# Koroliov_v2.net
KiCad netlist of a schematic drawn in EAGLE
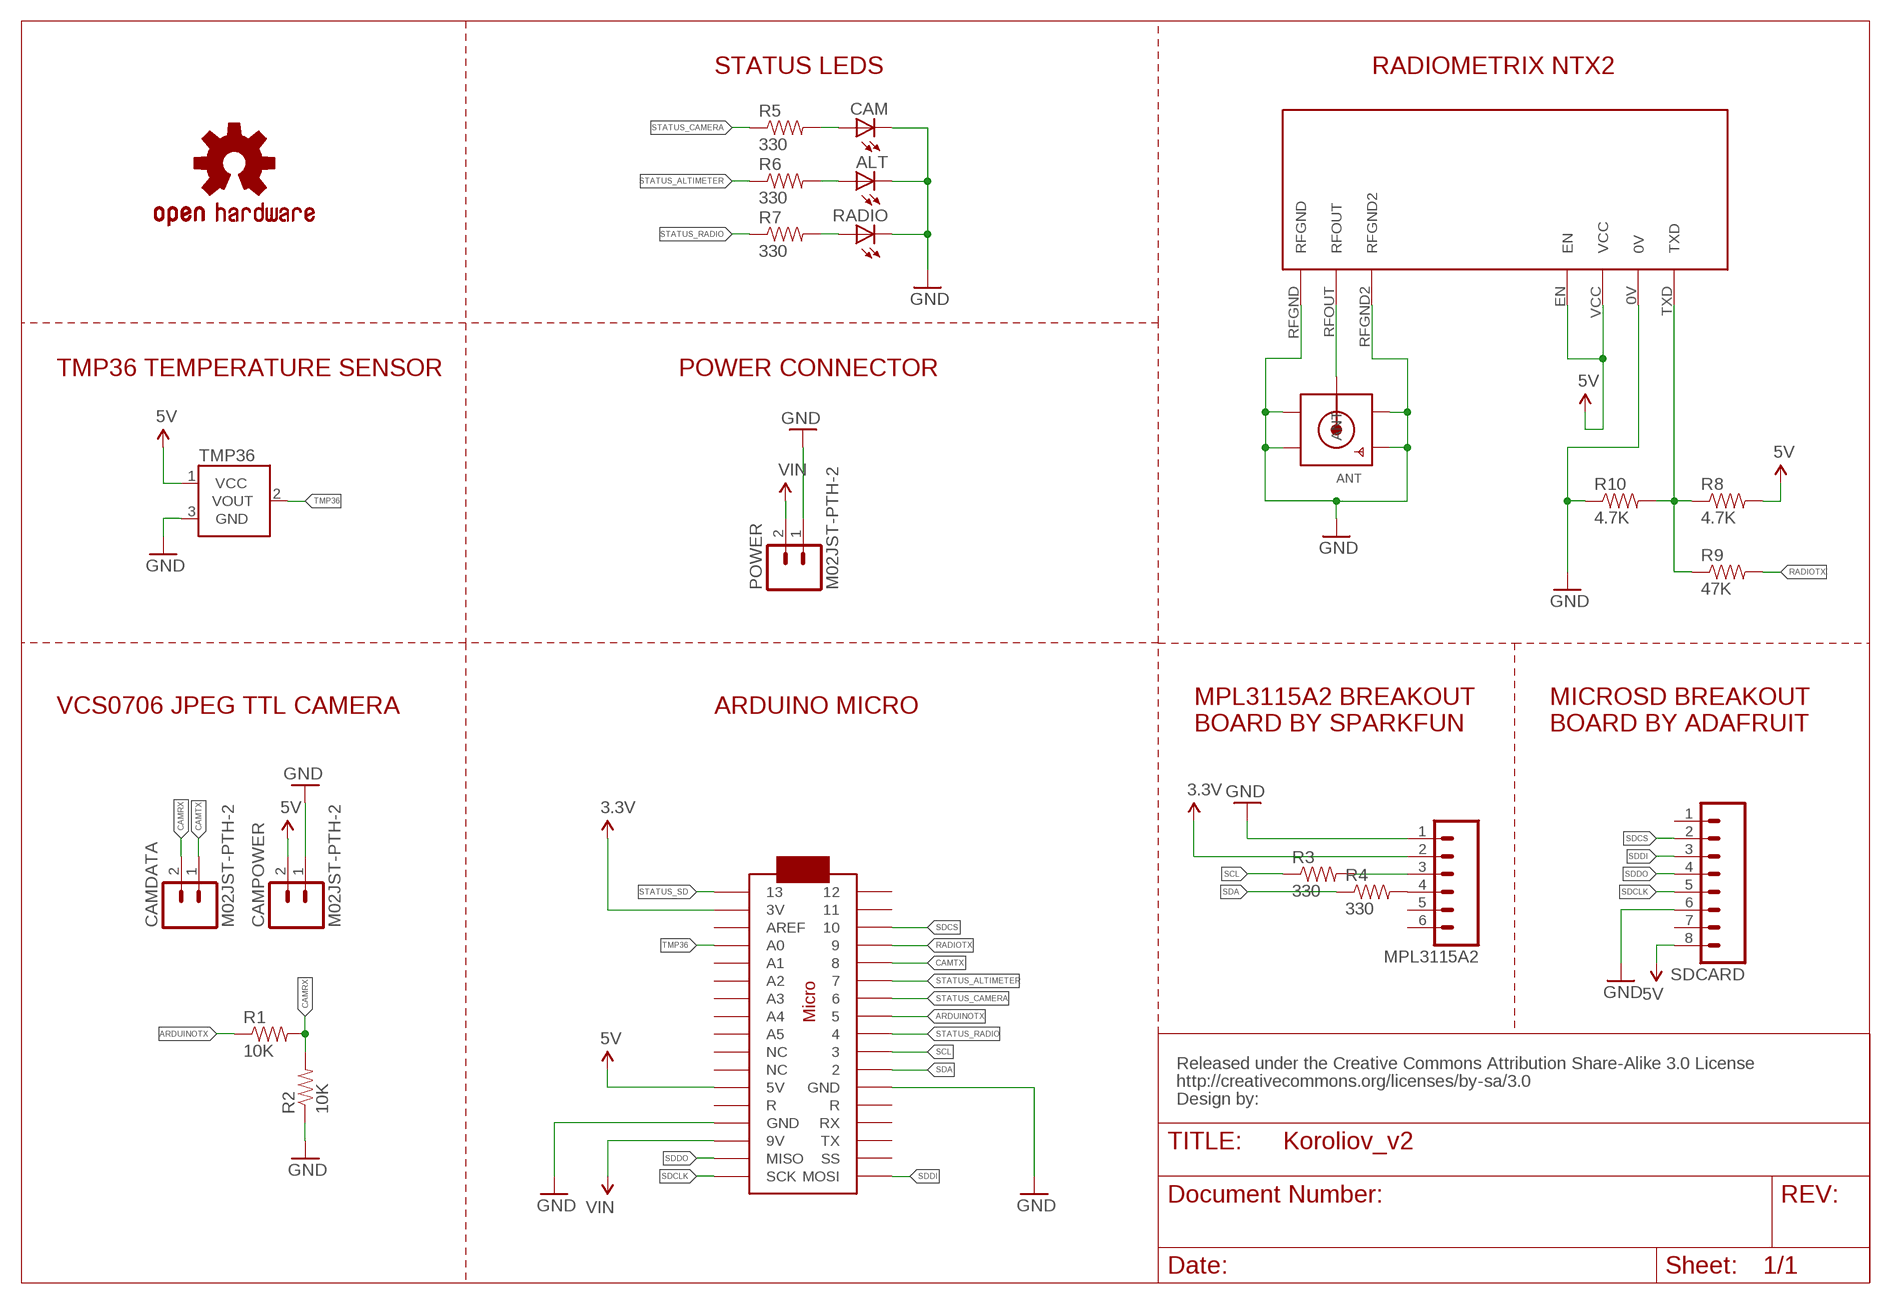
[diagram p0: schematic, sheet 1]

(export (version "E")
  (design (tool "Eeschema 10.0.6"))
  (components
    (comp (ref "ALT")
      (value "LED1206")
      (footprint "eagle-import:LED-1206")
      (libsource (lib "eagle-import") (part "LED1206"))
    )
    (comp (ref "ANT")
      (value "SMACONNECTOR_EDGE")
      (footprint "eagle-import:SMA_EDGELAUNCH")
      (libsource (lib "eagle-import") (part "SMACONNECTOR_EDGE"))
    )
    (comp (ref "ARDUINOMICRO")
      (value "ARDUINOMICRO")
      (footprint "eagle-import:ARDUINOMICRO")
      (libsource (lib "eagle-import") (part "ARDUINOMICRO"))
    )
    (comp (ref "CAM")
      (value "LED1206")
      (footprint "eagle-import:LED-1206")
      (libsource (lib "eagle-import") (part "LED1206"))
    )
    (comp (ref "CAMDATA")
      (value "M02JST-PTH-2")
      (footprint "eagle-import:JST-2-PTH")
      (libsource (lib "eagle-import") (part "M02JST-PTH-2"))
    )
    (comp (ref "CAMPOWER")
      (value "M02JST-PTH-2")
      (footprint "eagle-import:JST-2-PTH")
      (libsource (lib "eagle-import") (part "M02JST-PTH-2"))
    )
    (comp (ref "CC_TEXT1")
      (value "CREATIVE_COMMONS")
      (footprint "eagle-import:CREATIVE_COMMONS")
      (libsource (lib "eagle-import") (part "CREATIVE_COMMONS"))
    )
    (comp (ref "LOGO1")
      (value "OSHW-LOGOL")
      (footprint "eagle-import:OSHW-LOGO-L")
      (libsource (lib "eagle-import") (part "OSHW-LOGOL"))
    )
    (comp (ref "MPL3115A2")
      (value "M06SIP")
      (footprint "eagle-import:1X06")
      (libsource (lib "eagle-import") (part "M06SIP"))
    )
    (comp (ref "NTX2")
      (value "NTX2")
      (footprint "eagle-import:NTX2")
      (libsource (lib "eagle-import") (part "NTX2"))
    )
    (comp (ref "POWER")
      (value "M02JST-PTH-2")
      (footprint "eagle-import:JST-2-PTH")
      (libsource (lib "eagle-import") (part "M02JST-PTH-2"))
    )
    (comp (ref "R1")
      (value "10K")
      (footprint "eagle-import:1206")
      (libsource (lib "eagle-import") (part "RESISTOR1206"))
    )
    (comp (ref "R2")
      (value "10K")
      (footprint "eagle-import:1206")
      (libsource (lib "eagle-import") (part "RESISTOR1206"))
    )
    (comp (ref "R3")
      (value "330")
      (footprint "eagle-import:1206")
      (libsource (lib "eagle-import") (part "RESISTOR1206"))
    )
    (comp (ref "R4")
      (value "330")
      (footprint "eagle-import:1206")
      (libsource (lib "eagle-import") (part "RESISTOR1206"))
    )
    (comp (ref "R5")
      (value "330")
      (footprint "eagle-import:1206")
      (libsource (lib "eagle-import") (part "RESISTOR1206"))
    )
    (comp (ref "R6")
      (value "330")
      (footprint "eagle-import:1206")
      (libsource (lib "eagle-import") (part "RESISTOR1206"))
    )
    (comp (ref "R7")
      (value "330")
      (footprint "eagle-import:1206")
      (libsource (lib "eagle-import") (part "RESISTOR1206"))
    )
    (comp (ref "R8")
      (value "4.7K")
      (footprint "eagle-import:1206")
      (libsource (lib "eagle-import") (part "RESISTOR1206"))
    )
    (comp (ref "R9")
      (value "47K")
      (footprint "eagle-import:1206")
      (libsource (lib "eagle-import") (part "RESISTOR1206"))
    )
    (comp (ref "R10")
      (value "4.7K")
      (footprint "eagle-import:1206")
      (libsource (lib "eagle-import") (part "RESISTOR1206"))
    )
    (comp (ref "RADIO")
      (value "LED1206")
      (footprint "eagle-import:LED-1206")
      (libsource (lib "eagle-import") (part "LED1206"))
    )
    (comp (ref "SDCARD")
      (value "M081X08")
      (footprint "eagle-import:1X08")
      (libsource (lib "eagle-import") (part "M081X08"))
    )
    (comp (ref "TMP36")
      (value "TMP36GT9")
      (footprint "eagle-import:TO-92")
      (libsource (lib "eagle-import") (part "TMP36GT9"))
    )
  )
  (nets
    (net (code "1") (name "3.3V") (class "Default")
      (node (ref "ARDUINOMICRO") (pin "P$33") (pinfunction "3V_P$33") (pintype "bidirectional"))
      (node (ref "MPL3115A2") (pin "2") (pinfunction "2_2") (pintype "passive"))
    )
    (net (code "2") (name "5V") (class "Default")
      (node (ref "ARDUINOMICRO") (pin "P$23") (pinfunction "5V_P$23") (pintype "bidirectional"))
      (node (ref "CAMPOWER") (pin "2") (pinfunction "2_2") (pintype "passive"))
      (node (ref "NTX2") (pin "EN") (pinfunction "EN_EN") (pintype "bidirectional"))
      (node (ref "NTX2") (pin "VCC") (pinfunction "VCC_VCC") (pintype "bidirectional"))
      (node (ref "R8") (pin "2") (pinfunction "2_2") (pintype "passive"))
      (node (ref "SDCARD") (pin "8") (pinfunction "8_8") (pintype "passive"))
      (node (ref "TMP36") (pin "1") (pinfunction "VCC_1") (pintype "bidirectional"))
    )
    (net (code "3") (name "ARDUINOTX") (class "Default")
      (node (ref "ARDUINOMICRO") (pin "P$8") (pinfunction "5_P$8") (pintype "bidirectional"))
      (node (ref "R1") (pin "1") (pinfunction "1_1") (pintype "passive"))
    )
    (net (code "4") (name "CAMRX") (class "Default")
      (node (ref "CAMDATA") (pin "2") (pinfunction "2_2") (pintype "passive"))
      (node (ref "R1") (pin "2") (pinfunction "2_2") (pintype "passive"))
      (node (ref "R2") (pin "2") (pinfunction "2_2") (pintype "passive"))
    )
    (net (code "5") (name "CAMTX") (class "Default")
      (node (ref "ARDUINOMICRO") (pin "P$5") (pinfunction "8_P$5") (pintype "bidirectional"))
      (node (ref "CAMDATA") (pin "1") (pinfunction "1_1") (pintype "passive"))
    )
    (net (code "6") (name "GND") (class "Default")
      (node (ref "ALT") (pin "C") (pinfunction "C_C") (pintype "passive"))
      (node (ref "ANT") (pin "GND@1") (pinfunction "GND4_GND@1") (pintype "power_in"))
      (node (ref "ANT") (pin "GND@2") (pinfunction "GND3_GND@2") (pintype "power_in"))
      (node (ref "ANT") (pin "GND@3") (pinfunction "GND2_GND@3") (pintype "power_in"))
      (node (ref "ANT") (pin "GND@4") (pinfunction "GND1_GND@4") (pintype "power_in"))
      (node (ref "ARDUINOMICRO") (pin "P$12") (pinfunction "GND_P$12") (pintype "bidirectional"))
      (node (ref "ARDUINOMICRO") (pin "P$21") (pinfunction "GND_P$21") (pintype "bidirectional"))
      (node (ref "CAM") (pin "C") (pinfunction "C_C") (pintype "passive"))
      (node (ref "CAMPOWER") (pin "1") (pinfunction "1_1") (pintype "passive"))
      (node (ref "MPL3115A2") (pin "1") (pinfunction "1_1") (pintype "passive"))
      (node (ref "NTX2") (pin "0V") (pinfunction "0V_0V") (pintype "bidirectional"))
      (node (ref "NTX2") (pin "RFGND") (pinfunction "RFGND_RFGND") (pintype "bidirectional"))
      (node (ref "NTX2") (pin "RFGND2") (pinfunction "RFGND2_RFGND2") (pintype "bidirectional"))
      (node (ref "POWER") (pin "1") (pinfunction "1_1") (pintype "passive"))
      (node (ref "R10") (pin "1") (pinfunction "1_1") (pintype "passive"))
      (node (ref "R2") (pin "1") (pinfunction "1_1") (pintype "passive"))
      (node (ref "RADIO") (pin "C") (pinfunction "C_C") (pintype "passive"))
      (node (ref "SDCARD") (pin "6") (pinfunction "6_6") (pintype "passive"))
      (node (ref "TMP36") (pin "3") (pinfunction "GND_3") (pintype "bidirectional"))
    )
    (net (code "7") (name "Net-(ALT-PadA)") (class "Default")
      (node (ref "ALT") (pin "A") (pinfunction "A_A") (pintype "passive"))
      (node (ref "R6") (pin "2") (pinfunction "2_2") (pintype "passive"))
    )
    (net (code "8") (name "Net-(ANT-ANT)") (class "Default")
      (node (ref "ANT") (pin "P") (pinfunction "ANT_P") (pintype "bidirectional"))
      (node (ref "NTX2") (pin "RFOUT") (pinfunction "RFOUT_RFOUT") (pintype "bidirectional"))
    )
    (net (code "9") (name "Net-(CAM-PadA)") (class "Default")
      (node (ref "CAM") (pin "A") (pinfunction "A_A") (pintype "passive"))
      (node (ref "R5") (pin "2") (pinfunction "2_2") (pintype "passive"))
    )
    (net (code "10") (name "Net-(MPL3115A2-Pad3)") (class "Default")
      (node (ref "MPL3115A2") (pin "3") (pinfunction "3_3") (pintype "passive"))
      (node (ref "R3") (pin "2") (pinfunction "2_2") (pintype "passive"))
    )
    (net (code "11") (name "Net-(MPL3115A2-Pad4)") (class "Default")
      (node (ref "MPL3115A2") (pin "4") (pinfunction "4_4") (pintype "passive"))
      (node (ref "R4") (pin "2") (pinfunction "2_2") (pintype "passive"))
    )
    (net (code "12") (name "Net-(NTX2-PadTXD)") (class "Default")
      (node (ref "NTX2") (pin "TXD") (pinfunction "TXD_TXD") (pintype "bidirectional"))
      (node (ref "R10") (pin "2") (pinfunction "2_2") (pintype "passive"))
      (node (ref "R8") (pin "1") (pinfunction "1_1") (pintype "passive"))
      (node (ref "R9") (pin "1") (pinfunction "1_1") (pintype "passive"))
    )
    (net (code "13") (name "Net-(R7-Pad2)") (class "Default")
      (node (ref "R7") (pin "2") (pinfunction "2_2") (pintype "passive"))
      (node (ref "RADIO") (pin "A") (pinfunction "A_A") (pintype "passive"))
    )
    (net (code "14") (name "RADIOTX") (class "Default")
      (node (ref "ARDUINOMICRO") (pin "P$4") (pinfunction "9_P$4") (pintype "bidirectional"))
      (node (ref "R9") (pin "2") (pinfunction "2_2") (pintype "passive"))
    )
    (net (code "15") (name "SCL") (class "Default")
      (node (ref "ARDUINOMICRO") (pin "P$10") (pinfunction "3_P$10") (pintype "bidirectional"))
      (node (ref "R3") (pin "1") (pinfunction "1_1") (pintype "passive"))
    )
    (net (code "16") (name "SDA") (class "Default")
      (node (ref "ARDUINOMICRO") (pin "P$11") (pinfunction "2_P$11") (pintype "bidirectional"))
      (node (ref "R4") (pin "1") (pinfunction "1_1") (pintype "passive"))
    )
    (net (code "17") (name "SDCLK") (class "Default")
      (node (ref "ARDUINOMICRO") (pin "P$18") (pinfunction "SCK_P$18") (pintype "bidirectional"))
      (node (ref "SDCARD") (pin "5") (pinfunction "5_5") (pintype "passive"))
    )
    (net (code "18") (name "SDCS") (class "Default")
      (node (ref "ARDUINOMICRO") (pin "P$3") (pinfunction "10_P$3") (pintype "bidirectional"))
      (node (ref "SDCARD") (pin "2") (pinfunction "2_2") (pintype "passive"))
    )
    (net (code "19") (name "SDDI") (class "Default")
      (node (ref "ARDUINOMICRO") (pin "P$17") (pinfunction "MOSI_P$17") (pintype "bidirectional"))
      (node (ref "SDCARD") (pin "3") (pinfunction "3_3") (pintype "passive"))
    )
    (net (code "20") (name "SDDO") (class "Default")
      (node (ref "ARDUINOMICRO") (pin "P$19") (pinfunction "MISO_P$19") (pintype "bidirectional"))
      (node (ref "SDCARD") (pin "4") (pinfunction "4_4") (pintype "passive"))
    )
    (net (code "21") (name "STATUS_ALTIMETER") (class "Default")
      (node (ref "ARDUINOMICRO") (pin "P$6") (pinfunction "7_P$6") (pintype "bidirectional"))
      (node (ref "R6") (pin "1") (pinfunction "1_1") (pintype "passive"))
    )
    (net (code "22") (name "STATUS_CAMERA") (class "Default")
      (node (ref "ARDUINOMICRO") (pin "P$7") (pinfunction "6_P$7") (pintype "bidirectional"))
      (node (ref "R5") (pin "1") (pinfunction "1_1") (pintype "passive"))
    )
    (net (code "23") (name "STATUS_RADIO") (class "Default")
      (node (ref "ARDUINOMICRO") (pin "P$9") (pinfunction "4_P$9") (pintype "bidirectional"))
      (node (ref "R7") (pin "1") (pinfunction "1_1") (pintype "passive"))
    )
    (net (code "24") (name "STATUS_SD") (class "Default")
      (node (ref "ARDUINOMICRO") (pin "P$34") (pinfunction "13_P$34") (pintype "bidirectional"))
    )
    (net (code "25") (name "TMP36") (class "Default")
      (node (ref "ARDUINOMICRO") (pin "P$31") (pinfunction "A0_P$31") (pintype "bidirectional"))
      (node (ref "TMP36") (pin "2") (pinfunction "VOUT_2") (pintype "bidirectional"))
    )
    (net (code "26") (name "VIN") (class "Default")
      (node (ref "ARDUINOMICRO") (pin "P$20") (pinfunction "9V_P$20") (pintype "bidirectional"))
      (node (ref "POWER") (pin "2") (pinfunction "2_2") (pintype "passive"))
    )
    (net (code "27") (name "unconnected-(ARDUINOMICRO-11-PadP$2)") (class "Default")
      (node (ref "ARDUINOMICRO") (pin "P$2") (pinfunction "11_P$2") (pintype "bidirectional"))
    )
    (net (code "28") (name "unconnected-(ARDUINOMICRO-12-PadP$1)") (class "Default")
      (node (ref "ARDUINOMICRO") (pin "P$1") (pinfunction "12_P$1") (pintype "bidirectional"))
    )
    (net (code "29") (name "unconnected-(ARDUINOMICRO-A1-PadP$30)") (class "Default")
      (node (ref "ARDUINOMICRO") (pin "P$30") (pinfunction "A1_P$30") (pintype "bidirectional"))
    )
    (net (code "30") (name "unconnected-(ARDUINOMICRO-A2-PadP$29)") (class "Default")
      (node (ref "ARDUINOMICRO") (pin "P$29") (pinfunction "A2_P$29") (pintype "bidirectional"))
    )
    (net (code "31") (name "unconnected-(ARDUINOMICRO-A3-PadP$28)") (class "Default")
      (node (ref "ARDUINOMICRO") (pin "P$28") (pinfunction "A3_P$28") (pintype "bidirectional"))
    )
    (net (code "32") (name "unconnected-(ARDUINOMICRO-A4-PadP$27)") (class "Default")
      (node (ref "ARDUINOMICRO") (pin "P$27") (pinfunction "A4_P$27") (pintype "bidirectional"))
    )
    (net (code "33") (name "unconnected-(ARDUINOMICRO-A5-PadP$26)") (class "Default")
      (node (ref "ARDUINOMICRO") (pin "P$26") (pinfunction "A5_P$26") (pintype "bidirectional"))
    )
    (net (code "34") (name "unconnected-(ARDUINOMICRO-AREF-PadP$32)") (class "Default")
      (node (ref "ARDUINOMICRO") (pin "P$32") (pinfunction "AREF_P$32") (pintype "bidirectional"))
    )
    (net (code "35") (name "unconnected-(ARDUINOMICRO-NC-PadP$24)") (class "Default")
      (node (ref "ARDUINOMICRO") (pin "P$24") (pinfunction "NC_P$24") (pintype "bidirectional"))
    )
    (net (code "36") (name "unconnected-(ARDUINOMICRO-NC-PadP$25)") (class "Default")
      (node (ref "ARDUINOMICRO") (pin "P$25") (pinfunction "NC_P$25") (pintype "bidirectional"))
    )
    (net (code "37") (name "unconnected-(ARDUINOMICRO-R-PadP$13)") (class "Default")
      (node (ref "ARDUINOMICRO") (pin "P$13") (pinfunction "R_P$13") (pintype "bidirectional"))
    )
    (net (code "38") (name "unconnected-(ARDUINOMICRO-R-PadP$22)") (class "Default")
      (node (ref "ARDUINOMICRO") (pin "P$22") (pinfunction "R_P$22") (pintype "bidirectional"))
    )
    (net (code "39") (name "unconnected-(ARDUINOMICRO-RX-PadP$14)") (class "Default")
      (node (ref "ARDUINOMICRO") (pin "P$14") (pinfunction "RX_P$14") (pintype "bidirectional"))
    )
    (net (code "40") (name "unconnected-(ARDUINOMICRO-SS-PadP$16)") (class "Default")
      (node (ref "ARDUINOMICRO") (pin "P$16") (pinfunction "SS_P$16") (pintype "bidirectional"))
    )
    (net (code "41") (name "unconnected-(ARDUINOMICRO-TX-PadP$15)") (class "Default")
      (node (ref "ARDUINOMICRO") (pin "P$15") (pinfunction "TX_P$15") (pintype "bidirectional"))
    )
    (net (code "42") (name "unconnected-(MPL3115A2-Pad5)") (class "Default")
      (node (ref "MPL3115A2") (pin "5") (pinfunction "5_5") (pintype "passive"))
    )
    (net (code "43") (name "unconnected-(MPL3115A2-Pad6)") (class "Default")
      (node (ref "MPL3115A2") (pin "6") (pinfunction "6_6") (pintype "passive"))
    )
    (net (code "44") (name "unconnected-(SDCARD-Pad1)") (class "Default")
      (node (ref "SDCARD") (pin "1") (pinfunction "1_1") (pintype "passive"))
    )
    (net (code "45") (name "unconnected-(SDCARD-Pad7)") (class "Default")
      (node (ref "SDCARD") (pin "7") (pinfunction "7_7") (pintype "passive"))
    )
  )
)
